# Sheet1.net
KiCad netlist of a schematic drawn in Altium Designer
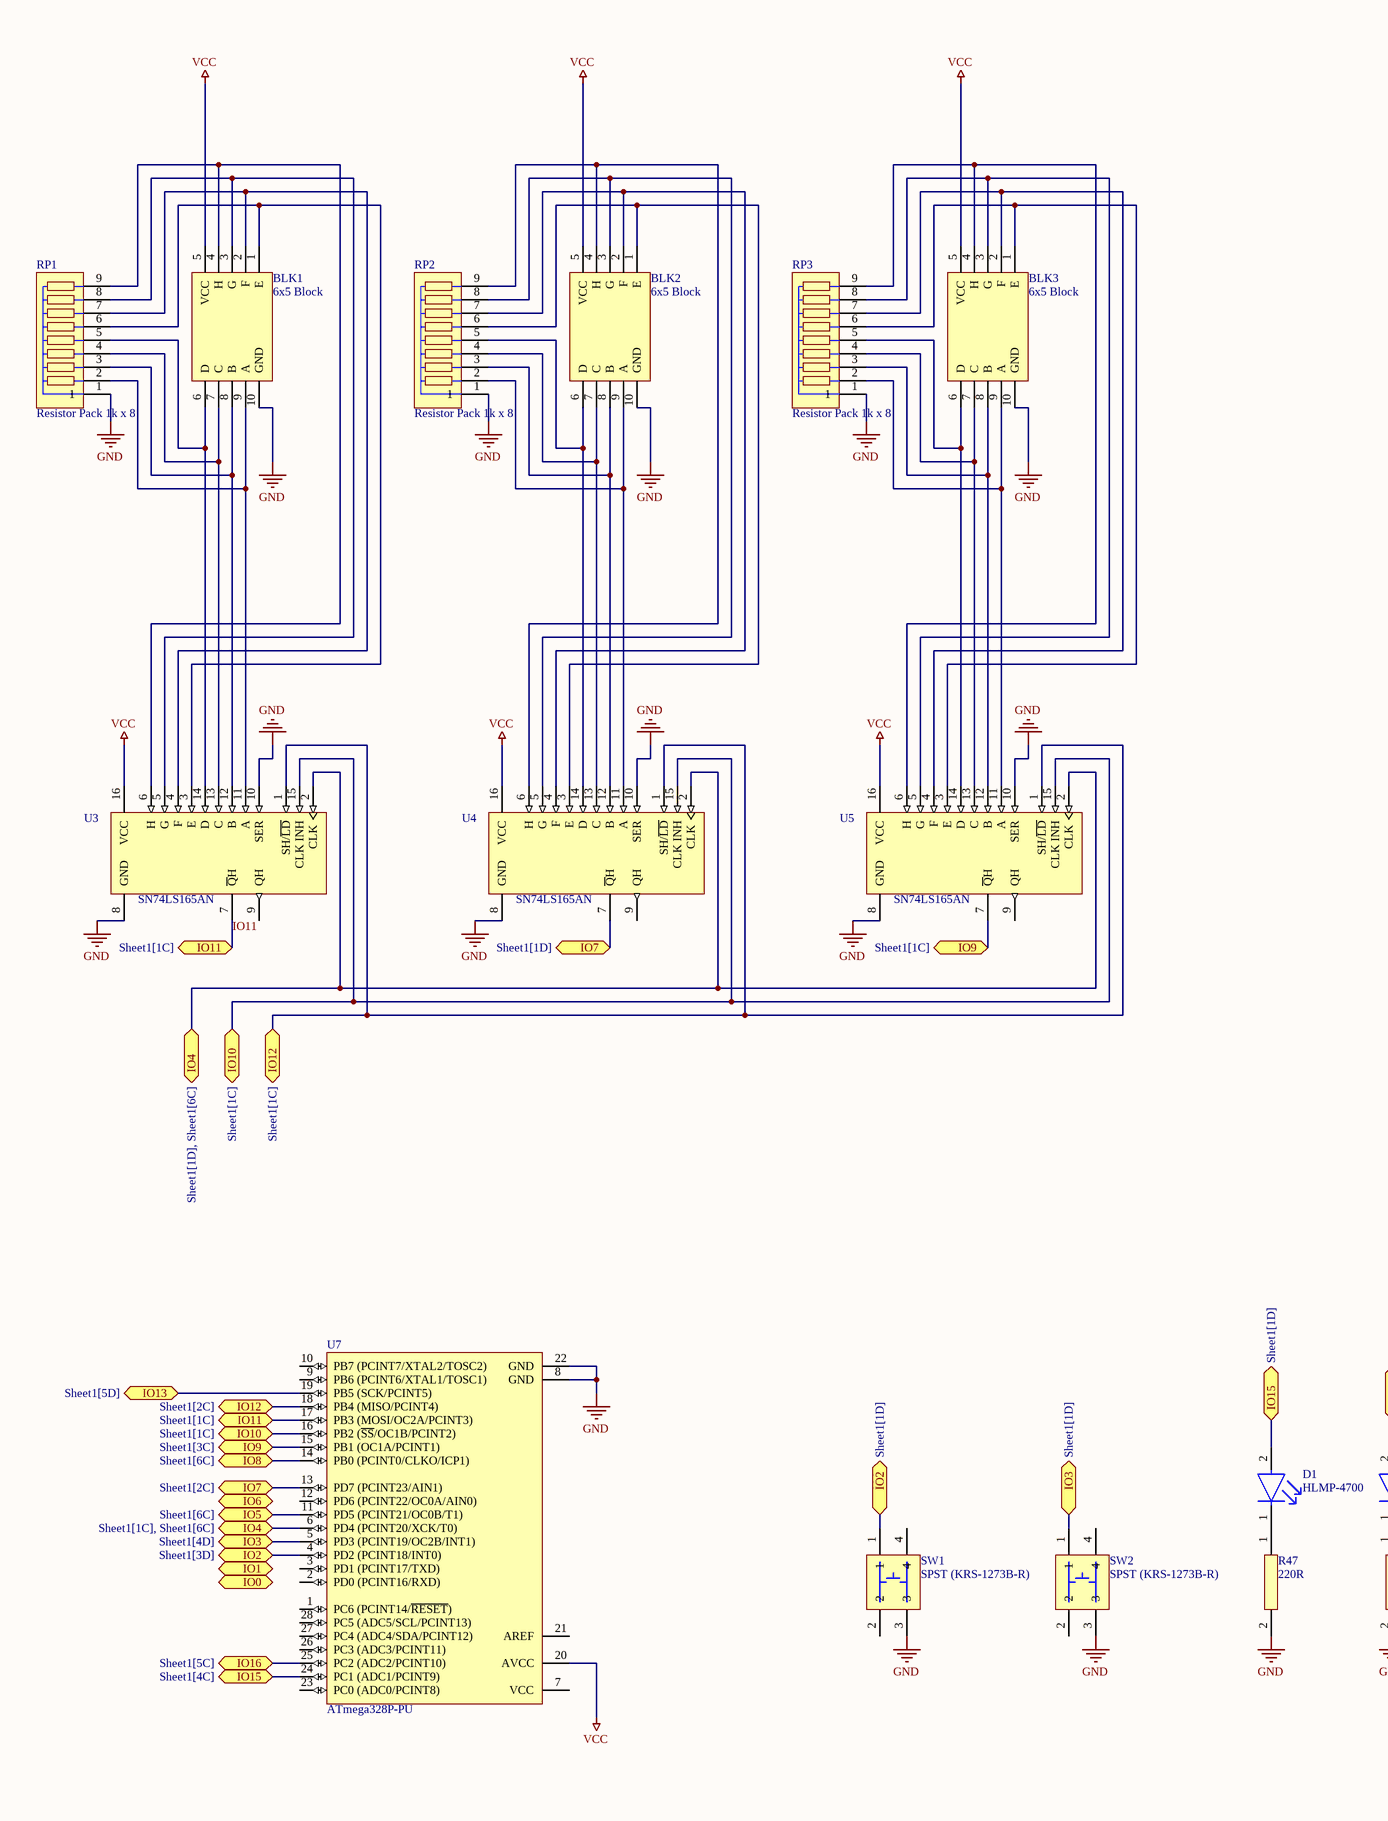
[diagram p0: Sheet1.SchDoc, left]
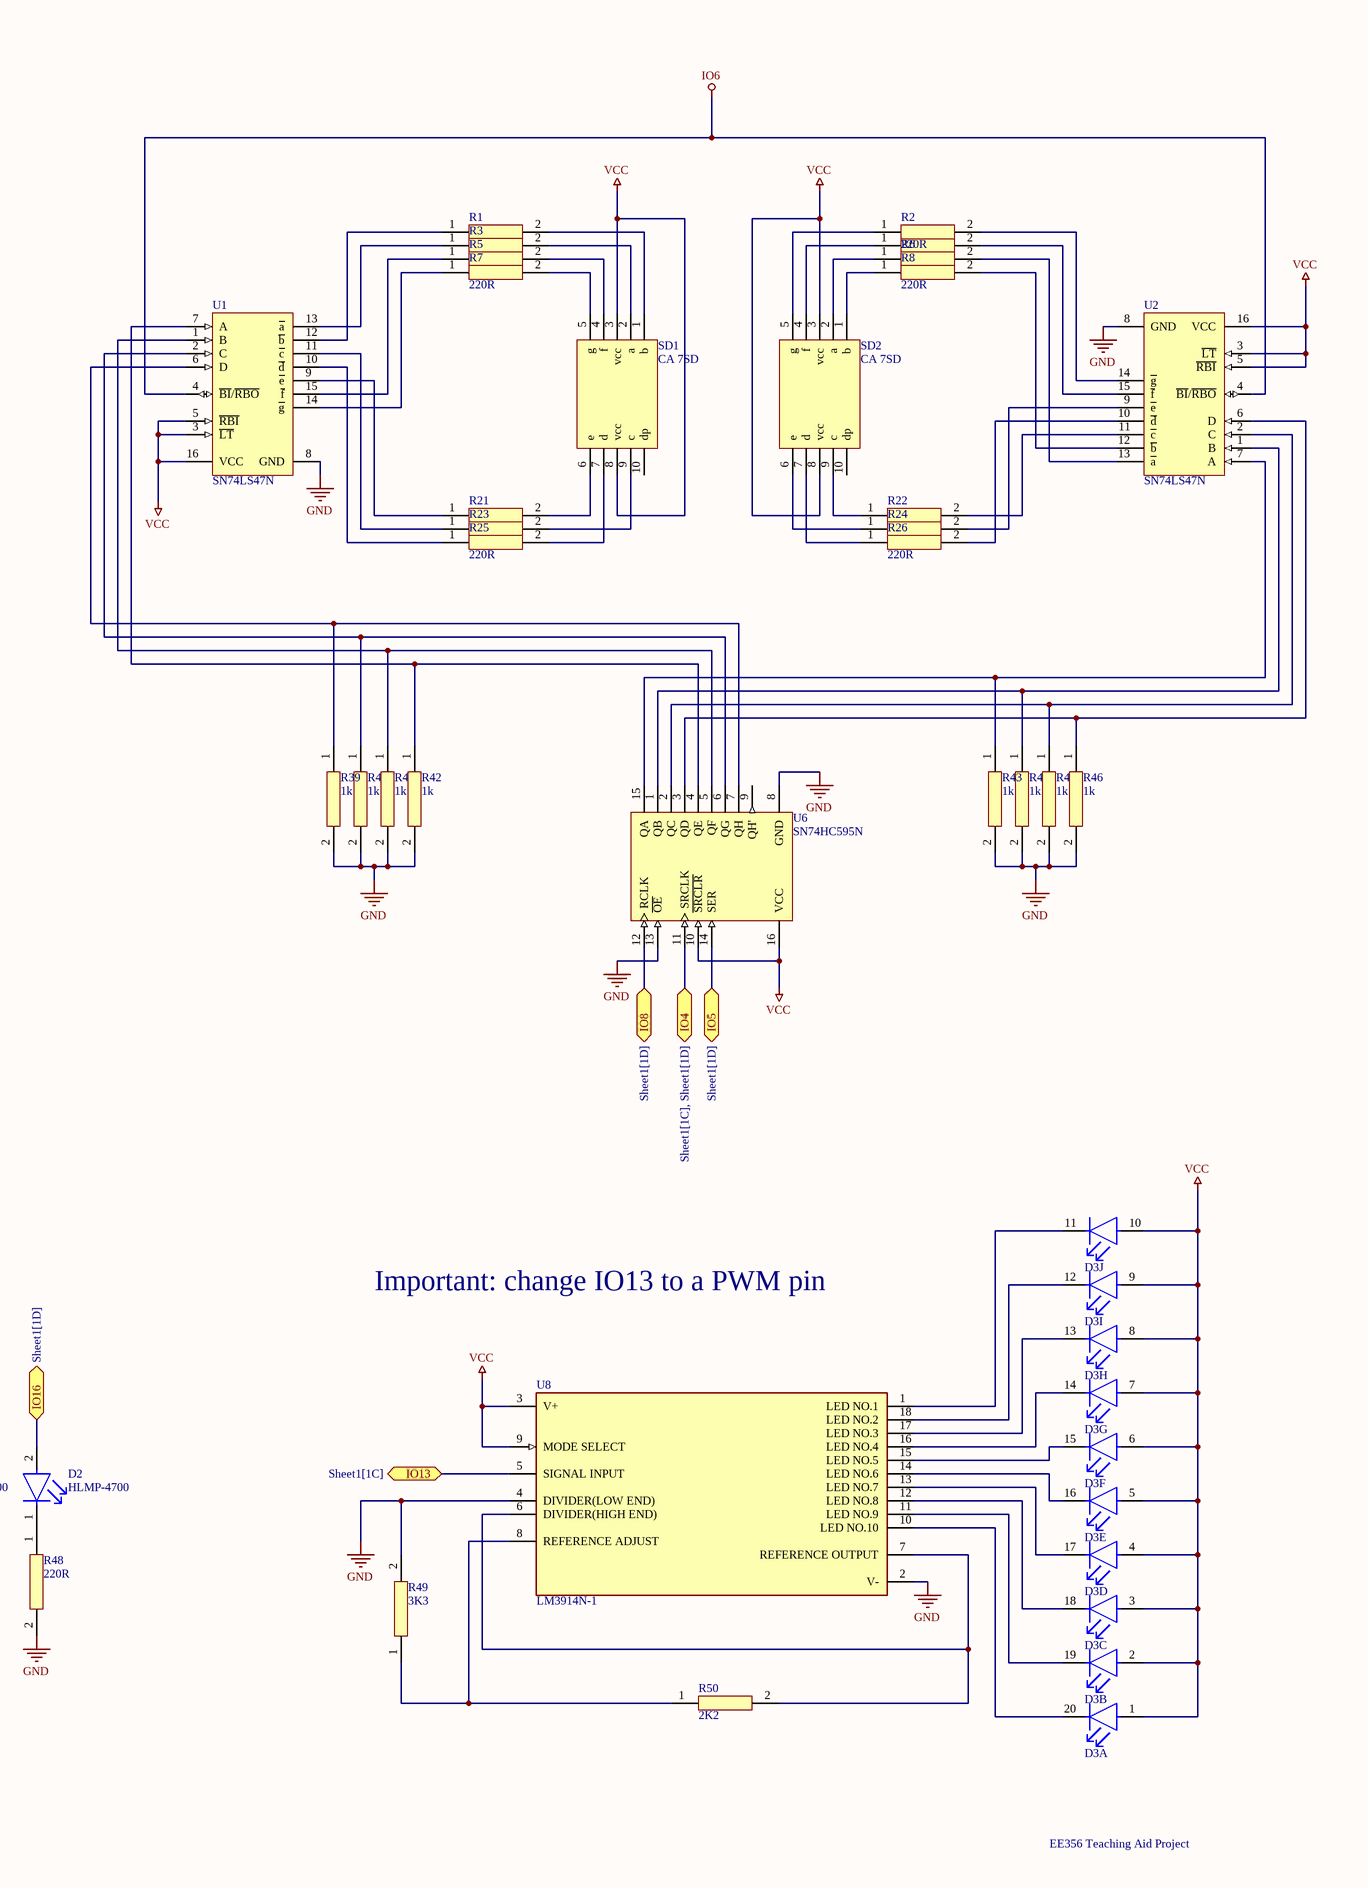
[diagram p1: Sheet1.SchDoc, right]

(export (version "E")
  (design (tool "Eeschema 10.0.6"))
  (components
    (comp (ref "BLK1")
      (value "6x5 Block")
      (footprint "Block_6x5")
      (libsource (lib "Schlib1") (part "Block_6x5"))
    )
    (comp (ref "BLK2")
      (value "6x5 Block")
      (footprint "Block_6x5")
      (libsource (lib "Schlib1") (part "Block_6x5"))
    )
    (comp (ref "BLK3")
      (value "6x5 Block")
      (footprint "Block_6x5")
      (libsource (lib "Schlib1") (part "Block_6x5"))
    )
    (comp (ref "D1")
      (value "HLMP-4700")
      (footprint "FP-HLMP-4700-MFG")
      (description "LED RED DIFFUSED T-1 3/4 T/H")
      (fields
        (field (name "OCTOPART") "https://octopart.com/hlmp-4700-broadcom-71130526")
        (field (name "MANUFACTURER") "Broadcom")
      )
      (libsource (lib "Altium Content Vault") (part "8706943c75ba83719d021d2fdc84c58"))
    )
    (comp (ref "D2")
      (value "HLMP-4700")
      (footprint "FP-HLMP-4700-MFG")
      (description "LED RED DIFFUSED T-1 3/4 T/H")
      (fields
        (field (name "OCTOPART") "https://octopart.com/hlmp-4700-broadcom-71130526")
        (field (name "MANUFACTURER") "Broadcom")
      )
      (libsource (lib "Altium Content Vault") (part "8706943c75ba83719d021d2fdc84c58"))
    )
    (comp (ref "D3")
      (value "SSA-LXB10HW-GF/LP")
      (footprint "FP-SSA-LXB10HW-GF-LP-MFG")
      (description "LED ARRAY 10X25MM 10SEG RED DIFF")
      (fields
        (field (name "OCTOPART") "https://octopart.com/ssa-lxb10hw-gf%2Flp-lumex-548235")
        (field (name "MANUFACTURER") "lumex")
      )
      (libsource (lib "Altium Content Vault") (part "0ad3f8813297581e4dba16f0763b6c7"))
    )
    (comp (ref "R1")
      (value "220R")
      (footprint "CFR_400mil")
      (description "General Type Carbon Film Resistor 220Ohm 1/4W 5% Axial Bulk")
      (fields
        (field (name "MANUFACTURER") "Yageo")
        (field (name "MANUFACTURER PART NUMBER") "CFR-25JB-52-220R")
      )
      (libsource (lib "Schlib1") (part "CFR-25JB-52-220R"))
    )
    (comp (ref "R2")
      (value "220R")
      (footprint "CFR_400mil")
      (description "General Type Carbon Film Resistor 220Ohm 1/4W 5% Axial Bulk")
      (fields
        (field (name "MANUFACTURER") "Yageo")
        (field (name "MANUFACTURER PART NUMBER") "CFR-25JB-52-220R")
      )
      (libsource (lib "Schlib1") (part "CFR-25JB-52-220R"))
    )
    (comp (ref "R3")
      (value "220R")
      (footprint "CFR_400mil")
      (description "General Type Carbon Film Resistor 220Ohm 1/4W 5% Axial Bulk")
      (fields
        (field (name "MANUFACTURER") "Yageo")
        (field (name "MANUFACTURER PART NUMBER") "CFR-25JB-52-220R")
      )
      (libsource (lib "Schlib1") (part "CFR-25JB-52-220R"))
    )
    (comp (ref "R4")
      (value "220R")
      (footprint "CFR_400mil")
      (description "General Type Carbon Film Resistor 220Ohm 1/4W 5% Axial Bulk")
      (fields
        (field (name "MANUFACTURER") "Yageo")
        (field (name "MANUFACTURER PART NUMBER") "CFR-25JB-52-220R")
      )
      (libsource (lib "Schlib1") (part "CFR-25JB-52-220R"))
    )
    (comp (ref "R5")
      (value "220R")
      (footprint "CFR_400mil")
      (description "General Type Carbon Film Resistor 220Ohm 1/4W 5% Axial Bulk")
      (fields
        (field (name "MANUFACTURER") "Yageo")
        (field (name "MANUFACTURER PART NUMBER") "CFR-25JB-52-220R")
      )
      (libsource (lib "Schlib1") (part "CFR-25JB-52-220R"))
    )
    (comp (ref "R6")
      (value "220R")
      (footprint "CFR_400mil")
      (description "General Type Carbon Film Resistor 220Ohm 1/4W 5% Axial Bulk")
      (fields
        (field (name "MANUFACTURER") "Yageo")
        (field (name "MANUFACTURER PART NUMBER") "CFR-25JB-52-220R")
      )
      (libsource (lib "Schlib1") (part "CFR-25JB-52-220R"))
    )
    (comp (ref "R7")
      (value "220R")
      (footprint "CFR_400mil")
      (description "General Type Carbon Film Resistor 220Ohm 1/4W 5% Axial Bulk")
      (fields
        (field (name "MANUFACTURER") "Yageo")
        (field (name "MANUFACTURER PART NUMBER") "CFR-25JB-52-220R")
      )
      (libsource (lib "Schlib1") (part "CFR-25JB-52-220R"))
    )
    (comp (ref "R8")
      (value "220R")
      (footprint "CFR_400mil")
      (description "General Type Carbon Film Resistor 220Ohm 1/4W 5% Axial Bulk")
      (fields
        (field (name "MANUFACTURER") "Yageo")
        (field (name "MANUFACTURER PART NUMBER") "CFR-25JB-52-220R")
      )
      (libsource (lib "Schlib1") (part "CFR-25JB-52-220R"))
    )
    (comp (ref "R21")
      (value "220R")
      (footprint "CFR_400mil")
      (description "General Type Carbon Film Resistor 220Ohm 1/4W 5% Axial Bulk")
      (fields
        (field (name "MANUFACTURER") "Yageo")
        (field (name "MANUFACTURER PART NUMBER") "CFR-25JB-52-220R")
      )
      (libsource (lib "Schlib1") (part "CFR-25JB-52-220R"))
    )
    (comp (ref "R22")
      (value "220R")
      (footprint "CFR_400mil")
      (description "General Type Carbon Film Resistor 220Ohm 1/4W 5% Axial Bulk")
      (fields
        (field (name "MANUFACTURER") "Yageo")
        (field (name "MANUFACTURER PART NUMBER") "CFR-25JB-52-220R")
      )
      (libsource (lib "Schlib1") (part "CFR-25JB-52-220R"))
    )
    (comp (ref "R23")
      (value "220R")
      (footprint "CFR_400mil")
      (description "General Type Carbon Film Resistor 220Ohm 1/4W 5% Axial Bulk")
      (fields
        (field (name "MANUFACTURER") "Yageo")
        (field (name "MANUFACTURER PART NUMBER") "CFR-25JB-52-220R")
      )
      (libsource (lib "Schlib1") (part "CFR-25JB-52-220R"))
    )
    (comp (ref "R24")
      (value "220R")
      (footprint "CFR_400mil")
      (description "General Type Carbon Film Resistor 220Ohm 1/4W 5% Axial Bulk")
      (fields
        (field (name "MANUFACTURER") "Yageo")
        (field (name "MANUFACTURER PART NUMBER") "CFR-25JB-52-220R")
      )
      (libsource (lib "Schlib1") (part "CFR-25JB-52-220R"))
    )
    (comp (ref "R25")
      (value "220R")
      (footprint "CFR_400mil")
      (description "General Type Carbon Film Resistor 220Ohm 1/4W 5% Axial Bulk")
      (fields
        (field (name "MANUFACTURER") "Yageo")
        (field (name "MANUFACTURER PART NUMBER") "CFR-25JB-52-220R")
      )
      (libsource (lib "Schlib1") (part "CFR-25JB-52-220R"))
    )
    (comp (ref "R26")
      (value "220R")
      (footprint "CFR_400mil")
      (description "General Type Carbon Film Resistor 220Ohm 1/4W 5% Axial Bulk")
      (fields
        (field (name "MANUFACTURER") "Yageo")
        (field (name "MANUFACTURER PART NUMBER") "CFR-25JB-52-220R")
      )
      (libsource (lib "Schlib1") (part "CFR-25JB-52-220R"))
    )
    (comp (ref "R39")
      (value "1k")
      (footprint "CFR_400mil")
      (description "Res Carbon Film 1K Ohm 5% 1/4W -350ppm/°C to 350ppm/°C Conformal AXL Thru-Hole Bulk")
      (fields
        (field (name "MANUFACTURER") "Yageo")
        (field (name "MANUFACTURER PART NUMBER") "CFR-25JB-52-1K")
      )
      (libsource (lib "Schlib1") (part "CFR-25JB-52-1K"))
    )
    (comp (ref "R40")
      (value "1k")
      (footprint "CFR_400mil")
      (description "Res Carbon Film 1K Ohm 5% 1/4W -350ppm/°C to 350ppm/°C Conformal AXL Thru-Hole Bulk")
      (fields
        (field (name "MANUFACTURER") "Yageo")
        (field (name "MANUFACTURER PART NUMBER") "CFR-25JB-52-1K")
      )
      (libsource (lib "Schlib1") (part "CFR-25JB-52-1K"))
    )
    (comp (ref "R41")
      (value "1k")
      (footprint "CFR_400mil")
      (description "Res Carbon Film 1K Ohm 5% 1/4W -350ppm/°C to 350ppm/°C Conformal AXL Thru-Hole Bulk")
      (fields
        (field (name "MANUFACTURER") "Yageo")
        (field (name "MANUFACTURER PART NUMBER") "CFR-25JB-52-1K")
      )
      (libsource (lib "Schlib1") (part "CFR-25JB-52-1K"))
    )
    (comp (ref "R42")
      (value "1k")
      (footprint "CFR_400mil")
      (description "Res Carbon Film 1K Ohm 5% 1/4W -350ppm/°C to 350ppm/°C Conformal AXL Thru-Hole Bulk")
      (fields
        (field (name "MANUFACTURER") "Yageo")
        (field (name "MANUFACTURER PART NUMBER") "CFR-25JB-52-1K")
      )
      (libsource (lib "Schlib1") (part "CFR-25JB-52-1K"))
    )
    (comp (ref "R43")
      (value "1k")
      (footprint "CFR_400mil")
      (description "Res Carbon Film 1K Ohm 5% 1/4W -350ppm/°C to 350ppm/°C Conformal AXL Thru-Hole Bulk")
      (fields
        (field (name "MANUFACTURER") "Yageo")
        (field (name "MANUFACTURER PART NUMBER") "CFR-25JB-52-1K")
      )
      (libsource (lib "Schlib1") (part "CFR-25JB-52-1K"))
    )
    (comp (ref "R44")
      (value "1k")
      (footprint "CFR_400mil")
      (description "Res Carbon Film 1K Ohm 5% 1/4W -350ppm/°C to 350ppm/°C Conformal AXL Thru-Hole Bulk")
      (fields
        (field (name "MANUFACTURER") "Yageo")
        (field (name "MANUFACTURER PART NUMBER") "CFR-25JB-52-1K")
      )
      (libsource (lib "Schlib1") (part "CFR-25JB-52-1K"))
    )
    (comp (ref "R45")
      (value "1k")
      (footprint "CFR_400mil")
      (description "Res Carbon Film 1K Ohm 5% 1/4W -350ppm/°C to 350ppm/°C Conformal AXL Thru-Hole Bulk")
      (fields
        (field (name "MANUFACTURER") "Yageo")
        (field (name "MANUFACTURER PART NUMBER") "CFR-25JB-52-1K")
      )
      (libsource (lib "Schlib1") (part "CFR-25JB-52-1K"))
    )
    (comp (ref "R46")
      (value "1k")
      (footprint "CFR_400mil")
      (description "Res Carbon Film 1K Ohm 5% 1/4W -350ppm/°C to 350ppm/°C Conformal AXL Thru-Hole Bulk")
      (fields
        (field (name "MANUFACTURER") "Yageo")
        (field (name "MANUFACTURER PART NUMBER") "CFR-25JB-52-1K")
      )
      (libsource (lib "Schlib1") (part "CFR-25JB-52-1K"))
    )
    (comp (ref "R47")
      (value "220R")
      (footprint "CFR_400mil")
      (description "General Type Carbon Film Resistor 220Ohm 1/4W 5% Axial Bulk")
      (fields
        (field (name "MANUFACTURER") "Yageo")
        (field (name "MANUFACTURER PART NUMBER") "CFR-25JB-52-220R")
      )
      (libsource (lib "") (part "CFR-25JB-52-220R_1"))
    )
    (comp (ref "R48")
      (value "220R")
      (footprint "CFR_400mil")
      (description "General Type Carbon Film Resistor 220Ohm 1/4W 5% Axial Bulk")
      (fields
        (field (name "MANUFACTURER") "Yageo")
        (field (name "MANUFACTURER PART NUMBER") "CFR-25JB-52-220R")
      )
      (libsource (lib "") (part "CFR-25JB-52-220R_1"))
    )
    (comp (ref "R49")
      (value "3K3")
      (footprint "CFR_400mil")
      (description "General Type Carbon Film Resistor 3.3kOhm 1/4W 5% Axial Bulk")
      (fields
        (field (name "MANUFACTURER") "Yageo")
        (field (name "MANUFACTURER PART NUMBER") "CFR-25JB-52-220R")
      )
      (libsource (lib "Schlib1") (part "CFR-25JB-52-3K3"))
    )
    (comp (ref "R50")
      (value "2K2")
      (footprint "CFR_400mil")
      (description "General Type Carbon Film Resistor 2.2kOhm 1/4W 5% Axial Bulk")
      (fields
        (field (name "MANUFACTURER") "Yageo")
        (field (name "MANUFACTURER PART NUMBER") "CFR-25JB-52-220R")
      )
      (libsource (lib "Schlib1") (part "CFR-25JB-52-2K2"))
    )
    (comp (ref "RP1")
      (value "Resistor Pack 1k x 8")
      (footprint "Resistor Pack 1k x 8")
      (description "Res Thick Film NET 1K Ohm 2% 1.13W ±100ppm/°C BUS Molded 9-Pin SIP Pin Thru-Hole")
      (fields
        (field (name "MANUFACTURER") "Bourns")
        (field (name "MANUFACTURER PART NUMBER") "4309R-101-102LF")
      )
      (libsource (lib "Schlib1") (part "4309R-101-102LF"))
    )
    (comp (ref "RP2")
      (value "Resistor Pack 1k x 8")
      (footprint "Resistor Pack 1k x 8")
      (description "Res Thick Film NET 1K Ohm 2% 1.13W ±100ppm/°C BUS Molded 9-Pin SIP Pin Thru-Hole")
      (fields
        (field (name "MANUFACTURER") "Bourns")
        (field (name "MANUFACTURER PART NUMBER") "4309R-101-102LF")
      )
      (libsource (lib "Schlib1") (part "4309R-101-102LF"))
    )
    (comp (ref "RP3")
      (value "Resistor Pack 1k x 8")
      (footprint "Resistor Pack 1k x 8")
      (description "Res Thick Film NET 1K Ohm 2% 1.13W ±100ppm/°C BUS Molded 9-Pin SIP Pin Thru-Hole")
      (fields
        (field (name "MANUFACTURER") "Bourns")
        (field (name "MANUFACTURER PART NUMBER") "4309R-101-102LF")
      )
      (libsource (lib "Schlib1") (part "4309R-101-102LF"))
    )
    (comp (ref "SD1")
      (value "CA 7SD")
      (footprint "CA 7SD")
      (description "Single Digit Seven Segment Green 0.56\" Common Anode Through Hole LED Display")
      (fields (field (name "MANUFACTURER") "Lumex") (field (name "MANUFACTURER PART NUMBER") "LDS-A5642RI"))
      (libsource (lib "Schlib1") (part "LDS-A5642RI"))
    )
    (comp (ref "SD2")
      (value "CA 7SD")
      (footprint "CA 7SD")
      (description "Single Digit Seven Segment Green 0.56\" Common Anode Through Hole LED Display")
      (fields (field (name "MANUFACTURER") "Lumex") (field (name "MANUFACTURER PART NUMBER") "LDS-A5642RI"))
      (libsource (lib "Schlib1") (part "LDS-A5642RI"))
    )
    (comp (ref "SW1")
      (value "SPST (KRS-1273B-R)")
      (footprint "SPST KRS-1273B-R")
      (description "Switch Push Button Tactile Off Momentary (On) Single Pole Single Throw Cap: 155389 155409")
      (fields
        (field (name "MANUFACTURER") "Jameco Valuepro")
        (field (name "MANUFACTURER PART NUMBER") "KRS-1273B-R")
      )
      (libsource (lib "Schlib1") (part "KRS-1273B-R"))
    )
    (comp (ref "SW2")
      (value "SPST (KRS-1273B-R)")
      (footprint "SPST KRS-1273B-R")
      (description "Switch Push Button Tactile Off Momentary (On) Single Pole Single Throw Cap: 155389 155409")
      (fields
        (field (name "MANUFACTURER") "Jameco Valuepro")
        (field (name "MANUFACTURER PART NUMBER") "KRS-1273B-R")
      )
      (libsource (lib "Schlib1") (part "KRS-1273B-R"))
    )
    (comp (ref "U1")
      (value "SN74LS47N")
      (footprint "N0016A")
      (description "BCD-to-7-Segment Decoder / Driver, 4.75 to 5.25 V, 0 to 70 degC, 16-pin DIP (N16), Pb-Free (RoHS)")
      (fields (field (name "MANUFACTURER") "Texas Instruments"))
      (libsource (lib "") (part "TI-SNX4XX247-16_1"))
    )
    (comp (ref "U2")
      (value "SN74LS47N")
      (footprint "N0016A")
      (description "BCD-to-7-Segment Decoder / Driver, 4.75 to 5.25 V, 0 to 70 degC, 16-pin DIP (N16), Pb-Free (RoHS)")
      (fields (field (name "MANUFACTURER") "Texas Instruments"))
      (libsource (lib "Altium Content Vault") (part "TI-SNX4XX247-16"))
    )
    (comp (ref "U3")
      (value "SN74LS165AN")
      (footprint "N0016A")
      (description "Serial-out shift registers, N0016A, TUBE")
      (fields
        (field (name "GENERIC PART NUMBER") "SN74LS165A")
        (field (name "MANUFACTURER") "Texas Instruments")
      )
      (libsource (lib "Altium Content Vault") (part "TI-SNX4XXX165X-16"))
    )
    (comp (ref "U4")
      (value "SN74LS165AN")
      (footprint "N0016A")
      (description "Serial-out shift registers, N0016A, TUBE")
      (fields
        (field (name "GENERIC PART NUMBER") "SN74LS165A")
        (field (name "MANUFACTURER") "Texas Instruments")
      )
      (libsource (lib "Altium Content Vault") (part "TI-SNX4XXX165X-16"))
    )
    (comp (ref "U5")
      (value "SN74LS165AN")
      (footprint "N0016A")
      (description "Serial-out shift registers, N0016A, TUBE")
      (fields
        (field (name "GENERIC PART NUMBER") "SN74LS165A")
        (field (name "MANUFACTURER") "Texas Instruments")
      )
      (libsource (lib "Altium Content Vault") (part "TI-SNX4XXX165X-16"))
    )
    (comp (ref "U6")
      (value "SN74HC595N")
      (footprint "N0016A")
      (description "8-Bit Shift Registers With 3-State Output Registers, N0016A, TUBE")
      (fields
        (field (name "GENERIC PART NUMBER") "SN74HC595")
        (field (name "MANUFACTURER") "Texas Instruments")
      )
      (libsource (lib "Altium Content Vault") (part "TI-SN74XHCT595X_SN74LV595A-16"))
    )
    (comp (ref "U7")
      (value "ATmega328P-PU")
      (footprint "28P3")
      (libsource (lib "Altium Content Vault") (part "MC-8B-ATM48-IL28"))
    )
    (comp (ref "U8")
      (value "LM3914N-1")
      (footprint "FP-NFK0018A-MFG")
      (description "IC DRVR DOT/BAR DISPLAY 18DIP")
      (libsource (lib "Altium Content Vault") (part "8d9105b9cf50def005be23956edfdd2"))
    )
  )
  (nets
    (net (code "3") (name "/IO2") (class "Default")
      (node (ref "SW1") (pin "1") (pinfunction "1_1") (pintype "passive"))
      (node (ref "U7") (pin "4") (pinfunction "PD2_(PCINT18/INT0)_4") (pintype "bidirectional"))
    )
    (net (code "4") (name "/IO3") (class "Default")
      (node (ref "SW2") (pin "1") (pinfunction "1_1") (pintype "passive"))
      (node (ref "U7") (pin "5") (pinfunction "PD3_(PCINT19/OC2B/INT1)_5") (pintype "bidirectional"))
    )
    (net (code "5") (name "/IO4") (class "Default")
      (node (ref "U3") (pin "2") (pinfunction "CLK_2") (pintype "input"))
      (node (ref "U4") (pin "2") (pinfunction "CLK_2") (pintype "input"))
      (node (ref "U5") (pin "2") (pinfunction "CLK_2") (pintype "input"))
      (node (ref "U6") (pin "11") (pinfunction "SRCLK_11") (pintype "input"))
      (node (ref "U7") (pin "6") (pinfunction "PD4_(PCINT20/XCK/T0)_6") (pintype "bidirectional"))
    )
    (net (code "6") (name "/IO5") (class "Default")
      (node (ref "U6") (pin "14") (pinfunction "SER_14") (pintype "input"))
      (node (ref "U7") (pin "11") (pinfunction "PD5_(PCINT21/OC0B/T1)_11") (pintype "bidirectional"))
    )
    (net (code "7") (name "/IO7") (class "Default")
      (node (ref "U4") (pin "7") (pinfunction "~{Q}H_7") (pintype "passive"))
      (node (ref "U7") (pin "13") (pinfunction "PD7_(PCINT23/AIN1)_13") (pintype "bidirectional"))
    )
    (net (code "8") (name "/IO8") (class "Default")
      (node (ref "U6") (pin "12") (pinfunction "RCLK_12") (pintype "input"))
      (node (ref "U7") (pin "14") (pinfunction "PB0_(PCINT0/CLKO/ICP1)_14") (pintype "bidirectional"))
    )
    (net (code "9") (name "/IO9") (class "Default")
      (node (ref "U5") (pin "7") (pinfunction "~{Q}H_7") (pintype "passive"))
      (node (ref "U7") (pin "15") (pinfunction "PB1_(OC1A/PCINT1)_15") (pintype "bidirectional"))
    )
    (net (code "10") (name "/IO10") (class "Default")
      (node (ref "U3") (pin "15") (pinfunction "CLK_INH_15") (pintype "input"))
      (node (ref "U4") (pin "15") (pinfunction "CLK_INH_15") (pintype "input"))
      (node (ref "U5") (pin "15") (pinfunction "CLK_INH_15") (pintype "input"))
      (node (ref "U7") (pin "16") (pinfunction "PB2_(~{SS}/OC1B/PCINT2)_16") (pintype "bidirectional"))
    )
    (net (code "11") (name "/IO11") (class "Default")
      (node (ref "U3") (pin "7") (pinfunction "~{Q}H_7") (pintype "passive"))
      (node (ref "U7") (pin "17") (pinfunction "PB3_(MOSI/OC2A/PCINT3)_17") (pintype "bidirectional"))
    )
    (net (code "12") (name "/IO12") (class "Default")
      (node (ref "U3") (pin "1") (pinfunction "SH/~{LD}_1") (pintype "input"))
      (node (ref "U4") (pin "1") (pinfunction "SH/~{LD}_1") (pintype "input"))
      (node (ref "U5") (pin "1") (pinfunction "SH/~{LD}_1") (pintype "input"))
      (node (ref "U7") (pin "18") (pinfunction "PB4_(MISO/PCINT4)_18") (pintype "bidirectional"))
    )
    (net (code "13") (name "/IO13") (class "Default")
      (node (ref "U7") (pin "19") (pinfunction "PB5_(SCK/PCINT5)_19") (pintype "bidirectional"))
      (node (ref "U8") (pin "5") (pinfunction "SIGNAL_INPUT_5") (pintype "passive"))
    )
    (net (code "14") (name "/IO15") (class "Default")
      (node (ref "D1") (pin "2") (pinfunction "A_2") (pintype "passive"))
      (node (ref "U7") (pin "24") (pinfunction "PC1_(ADC1/PCINT9)_24") (pintype "bidirectional"))
    )
    (net (code "15") (name "/IO16") (class "Default")
      (node (ref "D2") (pin "2") (pinfunction "A_2") (pintype "passive"))
      (node (ref "U7") (pin "25") (pinfunction "PC2_(ADC2/PCINT10)_25") (pintype "bidirectional"))
    )
    (net (code "16") (name "GND") (class "Default")
      (node (ref "BLK1") (pin "10") (pinfunction "GND_10") (pintype "passive"))
      (node (ref "BLK2") (pin "10") (pinfunction "GND_10") (pintype "passive"))
      (node (ref "BLK3") (pin "10") (pinfunction "GND_10") (pintype "passive"))
      (node (ref "R39") (pin "2") (pinfunction "2_2") (pintype "passive"))
      (node (ref "R40") (pin "2") (pinfunction "2_2") (pintype "passive"))
      (node (ref "R41") (pin "2") (pinfunction "2_2") (pintype "passive"))
      (node (ref "R42") (pin "2") (pinfunction "2_2") (pintype "passive"))
      (node (ref "R43") (pin "2") (pinfunction "2_2") (pintype "passive"))
      (node (ref "R44") (pin "2") (pinfunction "2_2") (pintype "passive"))
      (node (ref "R45") (pin "2") (pinfunction "2_2") (pintype "passive"))
      (node (ref "R46") (pin "2") (pinfunction "2_2") (pintype "passive"))
      (node (ref "R47") (pin "2") (pinfunction "2_2") (pintype "passive"))
      (node (ref "R48") (pin "2") (pinfunction "2_2") (pintype "passive"))
      (node (ref "R49") (pin "2") (pinfunction "2_2") (pintype "passive"))
      (node (ref "RP1") (pin "1") (pinfunction "1_1") (pintype "passive"))
      (node (ref "RP2") (pin "1") (pinfunction "1_1") (pintype "passive"))
      (node (ref "RP3") (pin "1") (pinfunction "1_1") (pintype "passive"))
      (node (ref "SW1") (pin "3") (pinfunction "3_3") (pintype "passive"))
      (node (ref "SW2") (pin "3") (pinfunction "3_3") (pintype "passive"))
      (node (ref "U1") (pin "8") (pinfunction "GND_8") (pintype "power_in"))
      (node (ref "U2") (pin "8") (pinfunction "GND_8") (pintype "power_in"))
      (node (ref "U3") (pin "10") (pinfunction "SER_10") (pintype "input"))
      (node (ref "U3") (pin "8") (pinfunction "GND_8") (pintype "power_in"))
      (node (ref "U4") (pin "10") (pinfunction "SER_10") (pintype "input"))
      (node (ref "U4") (pin "8") (pinfunction "GND_8") (pintype "power_in"))
      (node (ref "U5") (pin "10") (pinfunction "SER_10") (pintype "input"))
      (node (ref "U5") (pin "8") (pinfunction "GND_8") (pintype "power_in"))
      (node (ref "U6") (pin "13") (pinfunction "~{OE}_13") (pintype "input"))
      (node (ref "U6") (pin "8") (pinfunction "GND_8") (pintype "power_in"))
      (node (ref "U7") (pin "22") (pinfunction "GND_22") (pintype "power_in"))
      (node (ref "U7") (pin "8") (pinfunction "GND_8") (pintype "power_in"))
      (node (ref "U8") (pin "2") (pinfunction "V-_2") (pintype "power_in"))
      (node (ref "U8") (pin "4") (pinfunction "DIVIDER(LOW_END)_4") (pintype "passive"))
    )
    (net (code "17") (name "IO6") (class "Default")
      (node (ref "U1") (pin "4") (pinfunction "~{BI}/~{RBO}_4") (pintype "bidirectional"))
      (node (ref "U2") (pin "4") (pinfunction "~{BI}/~{RBO}_4") (pintype "bidirectional"))
    )
    (net (code "18") (name "Net-(BLK1-A)") (class "Default")
      (node (ref "BLK1") (pin "9") (pinfunction "A_9") (pintype "passive"))
      (node (ref "RP1") (pin "2") (pinfunction "2_2") (pintype "passive"))
      (node (ref "U3") (pin "11") (pinfunction "A_11") (pintype "input"))
    )
    (net (code "19") (name "Net-(BLK1-B)") (class "Default")
      (node (ref "BLK1") (pin "8") (pinfunction "B_8") (pintype "passive"))
      (node (ref "RP1") (pin "3") (pinfunction "3_3") (pintype "passive"))
      (node (ref "U3") (pin "12") (pinfunction "B_12") (pintype "input"))
    )
    (net (code "20") (name "Net-(BLK1-C)") (class "Default")
      (node (ref "BLK1") (pin "7") (pinfunction "C_7") (pintype "passive"))
      (node (ref "RP1") (pin "4") (pinfunction "4_4") (pintype "passive"))
      (node (ref "U3") (pin "13") (pinfunction "C_13") (pintype "input"))
    )
    (net (code "21") (name "Net-(BLK1-D)") (class "Default")
      (node (ref "BLK1") (pin "6") (pinfunction "D_6") (pintype "passive"))
      (node (ref "RP1") (pin "5") (pinfunction "5_5") (pintype "passive"))
      (node (ref "U3") (pin "14") (pinfunction "D_14") (pintype "input"))
    )
    (net (code "22") (name "Net-(BLK1-E)") (class "Default")
      (node (ref "BLK1") (pin "1") (pinfunction "E_1") (pintype "passive"))
      (node (ref "RP1") (pin "6") (pinfunction "6_6") (pintype "passive"))
      (node (ref "U3") (pin "3") (pinfunction "E_3") (pintype "input"))
    )
    (net (code "23") (name "Net-(BLK1-F)") (class "Default")
      (node (ref "BLK1") (pin "2") (pinfunction "F_2") (pintype "passive"))
      (node (ref "RP1") (pin "7") (pinfunction "7_7") (pintype "passive"))
      (node (ref "U3") (pin "4") (pinfunction "F_4") (pintype "input"))
    )
    (net (code "24") (name "Net-(BLK1-G)") (class "Default")
      (node (ref "BLK1") (pin "3") (pinfunction "G_3") (pintype "passive"))
      (node (ref "RP1") (pin "8") (pinfunction "8_8") (pintype "passive"))
      (node (ref "U3") (pin "5") (pinfunction "G_5") (pintype "input"))
    )
    (net (code "25") (name "Net-(BLK1-H)") (class "Default")
      (node (ref "BLK1") (pin "4") (pinfunction "H_4") (pintype "passive"))
      (node (ref "RP1") (pin "9") (pinfunction "9_9") (pintype "passive"))
      (node (ref "U3") (pin "6") (pinfunction "H_6") (pintype "input"))
    )
    (net (code "26") (name "Net-(BLK2-A)") (class "Default")
      (node (ref "BLK2") (pin "9") (pinfunction "A_9") (pintype "passive"))
      (node (ref "RP2") (pin "2") (pinfunction "2_2") (pintype "passive"))
      (node (ref "U4") (pin "11") (pinfunction "A_11") (pintype "input"))
    )
    (net (code "27") (name "Net-(BLK2-B)") (class "Default")
      (node (ref "BLK2") (pin "8") (pinfunction "B_8") (pintype "passive"))
      (node (ref "RP2") (pin "3") (pinfunction "3_3") (pintype "passive"))
      (node (ref "U4") (pin "12") (pinfunction "B_12") (pintype "input"))
    )
    (net (code "28") (name "Net-(BLK2-C)") (class "Default")
      (node (ref "BLK2") (pin "7") (pinfunction "C_7") (pintype "passive"))
      (node (ref "RP2") (pin "4") (pinfunction "4_4") (pintype "passive"))
      (node (ref "U4") (pin "13") (pinfunction "C_13") (pintype "input"))
    )
    (net (code "29") (name "Net-(BLK2-D)") (class "Default")
      (node (ref "BLK2") (pin "6") (pinfunction "D_6") (pintype "passive"))
      (node (ref "RP2") (pin "5") (pinfunction "5_5") (pintype "passive"))
      (node (ref "U4") (pin "14") (pinfunction "D_14") (pintype "input"))
    )
    (net (code "30") (name "Net-(BLK2-E)") (class "Default")
      (node (ref "BLK2") (pin "1") (pinfunction "E_1") (pintype "passive"))
      (node (ref "RP2") (pin "6") (pinfunction "6_6") (pintype "passive"))
      (node (ref "U4") (pin "3") (pinfunction "E_3") (pintype "input"))
    )
    (net (code "31") (name "Net-(BLK2-F)") (class "Default")
      (node (ref "BLK2") (pin "2") (pinfunction "F_2") (pintype "passive"))
      (node (ref "RP2") (pin "7") (pinfunction "7_7") (pintype "passive"))
      (node (ref "U4") (pin "4") (pinfunction "F_4") (pintype "input"))
    )
    (net (code "32") (name "Net-(BLK2-G)") (class "Default")
      (node (ref "BLK2") (pin "3") (pinfunction "G_3") (pintype "passive"))
      (node (ref "RP2") (pin "8") (pinfunction "8_8") (pintype "passive"))
      (node (ref "U4") (pin "5") (pinfunction "G_5") (pintype "input"))
    )
    (net (code "33") (name "Net-(BLK2-H)") (class "Default")
      (node (ref "BLK2") (pin "4") (pinfunction "H_4") (pintype "passive"))
      (node (ref "RP2") (pin "9") (pinfunction "9_9") (pintype "passive"))
      (node (ref "U4") (pin "6") (pinfunction "H_6") (pintype "input"))
    )
    (net (code "34") (name "Net-(BLK3-A)") (class "Default")
      (node (ref "BLK3") (pin "9") (pinfunction "A_9") (pintype "passive"))
      (node (ref "RP3") (pin "2") (pinfunction "2_2") (pintype "passive"))
      (node (ref "U5") (pin "11") (pinfunction "A_11") (pintype "input"))
    )
    (net (code "35") (name "Net-(BLK3-B)") (class "Default")
      (node (ref "BLK3") (pin "8") (pinfunction "B_8") (pintype "passive"))
      (node (ref "RP3") (pin "3") (pinfunction "3_3") (pintype "passive"))
      (node (ref "U5") (pin "12") (pinfunction "B_12") (pintype "input"))
    )
    (net (code "36") (name "Net-(BLK3-C)") (class "Default")
      (node (ref "BLK3") (pin "7") (pinfunction "C_7") (pintype "passive"))
      (node (ref "RP3") (pin "4") (pinfunction "4_4") (pintype "passive"))
      (node (ref "U5") (pin "13") (pinfunction "C_13") (pintype "input"))
    )
    (net (code "37") (name "Net-(BLK3-D)") (class "Default")
      (node (ref "BLK3") (pin "6") (pinfunction "D_6") (pintype "passive"))
      (node (ref "RP3") (pin "5") (pinfunction "5_5") (pintype "passive"))
      (node (ref "U5") (pin "14") (pinfunction "D_14") (pintype "input"))
    )
    (net (code "38") (name "Net-(BLK3-E)") (class "Default")
      (node (ref "BLK3") (pin "1") (pinfunction "E_1") (pintype "passive"))
      (node (ref "RP3") (pin "6") (pinfunction "6_6") (pintype "passive"))
      (node (ref "U5") (pin "3") (pinfunction "E_3") (pintype "input"))
    )
    (net (code "39") (name "Net-(BLK3-F)") (class "Default")
      (node (ref "BLK3") (pin "2") (pinfunction "F_2") (pintype "passive"))
      (node (ref "RP3") (pin "7") (pinfunction "7_7") (pintype "passive"))
      (node (ref "U5") (pin "4") (pinfunction "F_4") (pintype "input"))
    )
    (net (code "40") (name "Net-(BLK3-G)") (class "Default")
      (node (ref "BLK3") (pin "3") (pinfunction "G_3") (pintype "passive"))
      (node (ref "RP3") (pin "8") (pinfunction "8_8") (pintype "passive"))
      (node (ref "U5") (pin "5") (pinfunction "G_5") (pintype "input"))
    )
    (net (code "41") (name "Net-(BLK3-H)") (class "Default")
      (node (ref "BLK3") (pin "4") (pinfunction "H_4") (pintype "passive"))
      (node (ref "RP3") (pin "9") (pinfunction "9_9") (pintype "passive"))
      (node (ref "U5") (pin "6") (pinfunction "H_6") (pintype "input"))
    )
    (net (code "42") (name "Net-(D1-C)") (class "Default")
      (node (ref "D1") (pin "1") (pinfunction "C_1") (pintype "passive"))
      (node (ref "R47") (pin "1") (pinfunction "1_1") (pintype "passive"))
    )
    (net (code "43") (name "Net-(D2-C)") (class "Default")
      (node (ref "D2") (pin "1") (pinfunction "C_1") (pintype "passive"))
      (node (ref "R48") (pin "1") (pinfunction "1_1") (pintype "passive"))
    )
    (net (code "44") (name "Net-(D3A-1_CATHODE)") (class "Default")
      (node (ref "D3") (pin "20") (pinfunction "1_CATHODE_20") (pintype "passive"))
      (node (ref "U8") (pin "10") (pinfunction "LED_NO.10_10") (pintype "passive"))
    )
    (net (code "45") (name "Net-(D3B-2_CATHODE)") (class "Default")
      (node (ref "D3") (pin "19") (pinfunction "2_CATHODE_19") (pintype "passive"))
      (node (ref "U8") (pin "11") (pinfunction "LED_NO.9_11") (pintype "passive"))
    )
    (net (code "46") (name "Net-(D3C-3_CATHODE)") (class "Default")
      (node (ref "D3") (pin "18") (pinfunction "3_CATHODE_18") (pintype "passive"))
      (node (ref "U8") (pin "12") (pinfunction "LED_NO.8_12") (pintype "passive"))
    )
    (net (code "47") (name "Net-(D3D-4_CATHODE)") (class "Default")
      (node (ref "D3") (pin "17") (pinfunction "4_CATHODE_17") (pintype "passive"))
      (node (ref "U8") (pin "13") (pinfunction "LED_NO.7_13") (pintype "passive"))
    )
    (net (code "48") (name "Net-(D3E-5_CATHODE)") (class "Default")
      (node (ref "D3") (pin "16") (pinfunction "5_CATHODE_16") (pintype "passive"))
      (node (ref "U8") (pin "14") (pinfunction "LED_NO.6_14") (pintype "passive"))
    )
    (net (code "49") (name "Net-(D3F-6_CATHODE)") (class "Default")
      (node (ref "D3") (pin "15") (pinfunction "6_CATHODE_15") (pintype "passive"))
      (node (ref "U8") (pin "15") (pinfunction "LED_NO.5_15") (pintype "passive"))
    )
    (net (code "50") (name "Net-(D3G-7_CATHODE)") (class "Default")
      (node (ref "D3") (pin "14") (pinfunction "7_CATHODE_14") (pintype "passive"))
      (node (ref "U8") (pin "16") (pinfunction "LED_NO.4_16") (pintype "passive"))
    )
    (net (code "51") (name "Net-(D3H-8_CATHODE)") (class "Default")
      (node (ref "D3") (pin "13") (pinfunction "8_CATHODE_13") (pintype "passive"))
      (node (ref "U8") (pin "17") (pinfunction "LED_NO.3_17") (pintype "passive"))
    )
    (net (code "52") (name "Net-(D3I-9_CATHODE)") (class "Default")
      (node (ref "D3") (pin "12") (pinfunction "9_CATHODE_12") (pintype "passive"))
      (node (ref "U8") (pin "18") (pinfunction "LED_NO.2_18") (pintype "passive"))
    )
    (net (code "53") (name "Net-(D3J-10_CATHODE)") (class "Default")
      (node (ref "D3") (pin "11") (pinfunction "10_CATHODE_11") (pintype "passive"))
      (node (ref "U8") (pin "1") (pinfunction "LED_NO.1_1") (pintype "passive"))
    )
    (net (code "54") (name "Net-(SD1-a)") (class "Default")
      (node (ref "R3") (pin "2") (pinfunction "2_2") (pintype "passive"))
      (node (ref "SD1") (pin "2") (pinfunction "a_2") (pintype "passive"))
    )
    (net (code "55") (name "Net-(SD1-b)") (class "Default")
      (node (ref "R1") (pin "2") (pinfunction "2_2") (pintype "passive"))
      (node (ref "SD1") (pin "1") (pinfunction "b_1") (pintype "passive"))
    )
    (net (code "56") (name "Net-(SD1-c)") (class "Default")
      (node (ref "R23") (pin "2") (pinfunction "2_2") (pintype "passive"))
      (node (ref "SD1") (pin "9") (pinfunction "c_9") (pintype "passive"))
    )
    (net (code "57") (name "Net-(SD1-d)") (class "Default")
      (node (ref "R25") (pin "2") (pinfunction "2_2") (pintype "passive"))
      (node (ref "SD1") (pin "7") (pinfunction "d_7") (pintype "passive"))
    )
    (net (code "58") (name "Net-(SD1-e)") (class "Default")
      (node (ref "R21") (pin "2") (pinfunction "2_2") (pintype "passive"))
      (node (ref "SD1") (pin "6") (pinfunction "e_6") (pintype "passive"))
    )
    (net (code "59") (name "Net-(SD1-f)") (class "Default")
      (node (ref "R5") (pin "2") (pinfunction "2_2") (pintype "passive"))
      (node (ref "SD1") (pin "4") (pinfunction "f_4") (pintype "passive"))
    )
    (net (code "60") (name "Net-(SD1-g)") (class "Default")
      (node (ref "R7") (pin "2") (pinfunction "2_2") (pintype "passive"))
      (node (ref "SD1") (pin "5") (pinfunction "g_5") (pintype "passive"))
    )
    (net (code "61") (name "Net-(SD2-a)") (class "Default")
      (node (ref "R6") (pin "1") (pinfunction "1_1") (pintype "passive"))
      (node (ref "SD2") (pin "2") (pinfunction "a_2") (pintype "passive"))
    )
    (net (code "62") (name "Net-(SD2-b)") (class "Default")
      (node (ref "R8") (pin "1") (pinfunction "1_1") (pintype "passive"))
      (node (ref "SD2") (pin "1") (pinfunction "b_1") (pintype "passive"))
    )
    (net (code "63") (name "Net-(SD2-c)") (class "Default")
      (node (ref "R22") (pin "1") (pinfunction "1_1") (pintype "passive"))
      (node (ref "SD2") (pin "9") (pinfunction "c_9") (pintype "passive"))
    )
    (net (code "64") (name "Net-(SD2-d)") (class "Default")
      (node (ref "R26") (pin "1") (pinfunction "1_1") (pintype "passive"))
      (node (ref "SD2") (pin "7") (pinfunction "d_7") (pintype "passive"))
    )
    (net (code "65") (name "Net-(SD2-e)") (class "Default")
      (node (ref "R24") (pin "1") (pinfunction "1_1") (pintype "passive"))
      (node (ref "SD2") (pin "6") (pinfunction "e_6") (pintype "passive"))
    )
    (net (code "66") (name "Net-(SD2-f)") (class "Default")
      (node (ref "R4") (pin "1") (pinfunction "1_1") (pintype "passive"))
      (node (ref "SD2") (pin "4") (pinfunction "f_4") (pintype "passive"))
    )
    (net (code "67") (name "Net-(SD2-g)") (class "Default")
      (node (ref "R2") (pin "1") (pinfunction "1_1") (pintype "passive"))
      (node (ref "SD2") (pin "5") (pinfunction "g_5") (pintype "passive"))
    )
    (net (code "68") (name "Net-(U1-A)") (class "Default")
      (node (ref "R42") (pin "1") (pinfunction "1_1") (pintype "passive"))
      (node (ref "U1") (pin "7") (pinfunction "A_7") (pintype "input"))
      (node (ref "U6") (pin "4") (pinfunction "QE_4") (pintype "tri_state"))
    )
    (net (code "69") (name "Net-(U1-B)") (class "Default")
      (node (ref "R41") (pin "1") (pinfunction "1_1") (pintype "passive"))
      (node (ref "U1") (pin "1") (pinfunction "B_1") (pintype "input"))
      (node (ref "U6") (pin "5") (pinfunction "QF_5") (pintype "tri_state"))
    )
    (net (code "70") (name "Net-(U1-C)") (class "Default")
      (node (ref "R40") (pin "1") (pinfunction "1_1") (pintype "passive"))
      (node (ref "U1") (pin "2") (pinfunction "C_2") (pintype "input"))
      (node (ref "U6") (pin "6") (pinfunction "QG_6") (pintype "tri_state"))
    )
    (net (code "71") (name "Net-(U1-D)") (class "Default")
      (node (ref "R39") (pin "1") (pinfunction "1_1") (pintype "passive"))
      (node (ref "U1") (pin "6") (pinfunction "D_6") (pintype "input"))
      (node (ref "U6") (pin "7") (pinfunction "QH_7") (pintype "tri_state"))
    )
    (net (code "72") (name "Net-(U1-~{a})") (class "Default")
      (node (ref "R3") (pin "1") (pinfunction "1_1") (pintype "passive"))
      (node (ref "U1") (pin "13") (pinfunction "~{a}_13") (pintype "open_collector"))
    )
    (net (code "73") (name "Net-(U1-~{b})") (class "Default")
      (node (ref "R1") (pin "1") (pinfunction "1_1") (pintype "passive"))
      (node (ref "U1") (pin "12") (pinfunction "~{b}_12") (pintype "open_collector"))
    )
    (net (code "74") (name "Net-(U1-~{c})") (class "Default")
      (node (ref "R23") (pin "1") (pinfunction "1_1") (pintype "passive"))
      (node (ref "U1") (pin "11") (pinfunction "~{c}_11") (pintype "open_collector"))
    )
    (net (code "75") (name "Net-(U1-~{d})") (class "Default")
      (node (ref "R25") (pin "1") (pinfunction "1_1") (pintype "passive"))
      (node (ref "U1") (pin "10") (pinfunction "~{d}_10") (pintype "open_collector"))
    )
    (net (code "76") (name "Net-(U1-~{e})") (class "Default")
      (node (ref "R21") (pin "1") (pinfunction "1_1") (pintype "passive"))
      (node (ref "U1") (pin "9") (pinfunction "~{e}_9") (pintype "open_collector"))
    )
    (net (code "77") (name "Net-(U1-~{f})") (class "Default")
      (node (ref "R5") (pin "1") (pinfunction "1_1") (pintype "passive"))
      (node (ref "U1") (pin "15") (pinfunction "~{f}_15") (pintype "open_collector"))
    )
    (net (code "78") (name "Net-(U1-~{g})") (class "Default")
      (node (ref "R7") (pin "1") (pinfunction "1_1") (pintype "passive"))
      (node (ref "U1") (pin "14") (pinfunction "~{g}_14") (pintype "open_collector"))
    )
    (net (code "79") (name "Net-(U2-A)") (class "Default")
      (node (ref "R43") (pin "1") (pinfunction "1_1") (pintype "passive"))
      (node (ref "U2") (pin "7") (pinfunction "A_7") (pintype "input"))
      (node (ref "U6") (pin "15") (pinfunction "QA_15") (pintype "tri_state"))
    )
    (net (code "80") (name "Net-(U2-B)") (class "Default")
      (node (ref "R44") (pin "1") (pinfunction "1_1") (pintype "passive"))
      (node (ref "U2") (pin "1") (pinfunction "B_1") (pintype "input"))
      (node (ref "U6") (pin "1") (pinfunction "QB_1") (pintype "tri_state"))
    )
    (net (code "81") (name "Net-(U2-C)") (class "Default")
      (node (ref "R45") (pin "1") (pinfunction "1_1") (pintype "passive"))
      (node (ref "U2") (pin "2") (pinfunction "C_2") (pintype "input"))
      (node (ref "U6") (pin "2") (pinfunction "QC_2") (pintype "tri_state"))
    )
    (net (code "82") (name "Net-(U2-D)") (class "Default")
      (node (ref "R46") (pin "1") (pinfunction "1_1") (pintype "passive"))
      (node (ref "U2") (pin "6") (pinfunction "D_6") (pintype "input"))
      (node (ref "U6") (pin "3") (pinfunction "QD_3") (pintype "tri_state"))
    )
    (net (code "83") (name "Net-(U2-~{a})") (class "Default")
      (node (ref "R6") (pin "2") (pinfunction "2_2") (pintype "passive"))
      (node (ref "U2") (pin "13") (pinfunction "~{a}_13") (pintype "open_collector"))
    )
    (net (code "84") (name "Net-(U2-~{b})") (class "Default")
      (node (ref "R8") (pin "2") (pinfunction "2_2") (pintype "passive"))
      (node (ref "U2") (pin "12") (pinfunction "~{b}_12") (pintype "open_collector"))
    )
    (net (code "85") (name "Net-(U2-~{c})") (class "Default")
      (node (ref "R22") (pin "2") (pinfunction "2_2") (pintype "passive"))
      (node (ref "U2") (pin "11") (pinfunction "~{c}_11") (pintype "open_collector"))
    )
    (net (code "86") (name "Net-(U2-~{d})") (class "Default")
      (node (ref "R26") (pin "2") (pinfunction "2_2") (pintype "passive"))
      (node (ref "U2") (pin "10") (pinfunction "~{d}_10") (pintype "open_collector"))
    )
    (net (code "87") (name "Net-(U2-~{e})") (class "Default")
      (node (ref "R24") (pin "2") (pinfunction "2_2") (pintype "passive"))
      (node (ref "U2") (pin "9") (pinfunction "~{e}_9") (pintype "open_collector"))
    )
    (net (code "88") (name "Net-(U2-~{f})") (class "Default")
      (node (ref "R4") (pin "2") (pinfunction "2_2") (pintype "passive"))
      (node (ref "U2") (pin "15") (pinfunction "~{f}_15") (pintype "open_collector"))
    )
    (net (code "89") (name "Net-(U2-~{g})") (class "Default")
      (node (ref "R2") (pin "2") (pinfunction "2_2") (pintype "passive"))
      (node (ref "U2") (pin "14") (pinfunction "~{g}_14") (pintype "open_collector"))
    )
    (net (code "90") (name "Net-(U8-DIVIDER(HIGH_END))") (class "Default")
      (node (ref "R50") (pin "2") (pinfunction "2_2") (pintype "passive"))
      (node (ref "U8") (pin "6") (pinfunction "DIVIDER(HIGH_END)_6") (pintype "passive"))
      (node (ref "U8") (pin "7") (pinfunction "REFERENCE_OUTPUT_7") (pintype "passive"))
    )
    (net (code "91") (name "Net-(U8-REFERENCE_ADJUST)") (class "Default")
      (node (ref "R49") (pin "1") (pinfunction "1_1") (pintype "passive"))
      (node (ref "R50") (pin "1") (pinfunction "1_1") (pintype "passive"))
      (node (ref "U8") (pin "8") (pinfunction "REFERENCE_ADJUST_8") (pintype "passive"))
    )
    (net (code "92") (name "VCC") (class "Default")
      (node (ref "BLK1") (pin "5") (pinfunction "VCC_5") (pintype "passive"))
      (node (ref "BLK2") (pin "5") (pinfunction "VCC_5") (pintype "passive"))
      (node (ref "BLK3") (pin "5") (pinfunction "VCC_5") (pintype "passive"))
      (node (ref "D3") (pin "1") (pinfunction "1_ANODE_1") (pintype "passive"))
      (node (ref "D3") (pin "10") (pinfunction "10_ANODE_10") (pintype "passive"))
      (node (ref "D3") (pin "2") (pinfunction "2_ANODE_2") (pintype "passive"))
      (node (ref "D3") (pin "3") (pinfunction "3_ANODE_3") (pintype "passive"))
      (node (ref "D3") (pin "4") (pinfunction "4_ANODE_4") (pintype "passive"))
      (node (ref "D3") (pin "5") (pinfunction "5_ANODE_5") (pintype "passive"))
      (node (ref "D3") (pin "6") (pinfunction "6_ANODE_6") (pintype "passive"))
      (node (ref "D3") (pin "7") (pinfunction "7_ANODE_7") (pintype "passive"))
      (node (ref "D3") (pin "8") (pinfunction "8_ANODE_8") (pintype "passive"))
      (node (ref "D3") (pin "9") (pinfunction "9_ANODE_9") (pintype "passive"))
      (node (ref "SD1") (pin "3") (pinfunction "vcc_3") (pintype "passive"))
      (node (ref "SD1") (pin "8") (pinfunction "vcc_8") (pintype "passive"))
      (node (ref "SD2") (pin "3") (pinfunction "vcc_3") (pintype "passive"))
      (node (ref "SD2") (pin "8") (pinfunction "vcc_8") (pintype "passive"))
      (node (ref "U1") (pin "16") (pinfunction "VCC_16") (pintype "power_in"))
      (node (ref "U1") (pin "3") (pinfunction "~{LT}_3") (pintype "input"))
      (node (ref "U1") (pin "5") (pinfunction "~{RBI}_5") (pintype "input"))
      (node (ref "U2") (pin "16") (pinfunction "VCC_16") (pintype "power_in"))
      (node (ref "U2") (pin "3") (pinfunction "~{LT}_3") (pintype "input"))
      (node (ref "U2") (pin "5") (pinfunction "~{RBI}_5") (pintype "input"))
      (node (ref "U3") (pin "16") (pinfunction "VCC_16") (pintype "power_in"))
      (node (ref "U4") (pin "16") (pinfunction "VCC_16") (pintype "power_in"))
      (node (ref "U5") (pin "16") (pinfunction "VCC_16") (pintype "power_in"))
      (node (ref "U6") (pin "10") (pinfunction "~{SRCLR}_10") (pintype "input"))
      (node (ref "U6") (pin "16") (pinfunction "VCC_16") (pintype "power_in"))
      (node (ref "U7") (pin "20") (pinfunction "AVCC_20") (pintype "power_in"))
      (node (ref "U8") (pin "3") (pinfunction "V+_3") (pintype "power_in"))
      (node (ref "U8") (pin "9") (pinfunction "MODE_SELECT_9") (pintype "input"))
    )
    (net (code "93") (name "unconnected-(SD1-dp-Pad10)") (class "Default")
      (node (ref "SD1") (pin "10") (pinfunction "dp_10") (pintype "passive"))
    )
    (net (code "94") (name "unconnected-(SD2-dp-Pad10)") (class "Default")
      (node (ref "SD2") (pin "10") (pinfunction "dp_10") (pintype "passive"))
    )
    (net (code "95") (name "unconnected-(SW1-Pad2)") (class "Default")
      (node (ref "SW1") (pin "2") (pinfunction "2_2") (pintype "passive"))
    )
    (net (code "96") (name "unconnected-(SW1-Pad4)") (class "Default")
      (node (ref "SW1") (pin "4") (pinfunction "4_4") (pintype "passive"))
    )
    (net (code "97") (name "unconnected-(SW2-Pad2)") (class "Default")
      (node (ref "SW2") (pin "2") (pinfunction "2_2") (pintype "passive"))
    )
    (net (code "98") (name "unconnected-(SW2-Pad4)") (class "Default")
      (node (ref "SW2") (pin "4") (pinfunction "4_4") (pintype "passive"))
    )
    (net (code "99") (name "unconnected-(U3-QH-Pad9)") (class "Default")
      (node (ref "U3") (pin "9") (pinfunction "QH_9") (pintype "output"))
    )
    (net (code "100") (name "unconnected-(U4-QH-Pad9)") (class "Default")
      (node (ref "U4") (pin "9") (pinfunction "QH_9") (pintype "output"))
    )
    (net (code "101") (name "unconnected-(U5-QH-Pad9)") (class "Default")
      (node (ref "U5") (pin "9") (pinfunction "QH_9") (pintype "output"))
    )
    (net (code "102") (name "unconnected-(U6-QH'-Pad9)") (class "Default")
      (node (ref "U6") (pin "9") (pinfunction "QH'_9") (pintype "output"))
    )
    (net (code "103") (name "unconnected-(U7-AREF-Pad21)") (class "Default")
      (node (ref "U7") (pin "21") (pinfunction "AREF_21") (pintype "power_in"))
    )
    (net (code "104") (name "unconnected-(U7-PB6_(PCINT6{slash}XTAL1{slash}TOSC1)-Pad9)") (class "Default")
      (node (ref "U7") (pin "9") (pinfunction "PB6_(PCINT6/XTAL1/TOSC1)_9") (pintype "bidirectional"))
    )
    (net (code "105") (name "unconnected-(U7-PB7_(PCINT7{slash}XTAL2{slash}TOSC2)-Pad10)") (class "Default")
      (node (ref "U7") (pin "10") (pinfunction "PB7_(PCINT7/XTAL2/TOSC2)_10") (pintype "bidirectional"))
    )
    (net (code "106") (name "unconnected-(U7-PC0_(ADC0{slash}PCINT8)-Pad23)") (class "Default")
      (node (ref "U7") (pin "23") (pinfunction "PC0_(ADC0/PCINT8)_23") (pintype "bidirectional"))
    )
    (net (code "107") (name "unconnected-(U7-PC3_(ADC3{slash}PCINT11)-Pad26)") (class "Default")
      (node (ref "U7") (pin "26") (pinfunction "PC3_(ADC3/PCINT11)_26") (pintype "bidirectional"))
    )
    (net (code "108") (name "unconnected-(U7-PC4_(ADC4{slash}SDA{slash}PCINT12)-Pad27)") (class "Default")
      (node (ref "U7") (pin "27") (pinfunction "PC4_(ADC4/SDA/PCINT12)_27") (pintype "bidirectional"))
    )
    (net (code "109") (name "unconnected-(U7-PC5_(ADC5{slash}SCL{slash}PCINT13)-Pad28)") (class "Default")
      (node (ref "U7") (pin "28") (pinfunction "PC5_(ADC5/SCL/PCINT13)_28") (pintype "bidirectional"))
    )
    (net (code "110") (name "unconnected-(U7-PC6_(PCINT14{slash}~{RESET})-Pad1)") (class "Default")
      (node (ref "U7") (pin "1") (pinfunction "PC6_(PCINT14/~{RESET})_1") (pintype "bidirectional"))
    )
    (net (code "111") (name "unconnected-(U7-PD0_(PCINT16{slash}RXD)-Pad2)") (class "Default")
      (node (ref "U7") (pin "2") (pinfunction "PD0_(PCINT16/RXD)_2") (pintype "bidirectional"))
    )
    (net (code "112") (name "unconnected-(U7-PD1_(PCINT17{slash}TXD)-Pad3)") (class "Default")
      (node (ref "U7") (pin "3") (pinfunction "PD1_(PCINT17/TXD)_3") (pintype "bidirectional"))
    )
    (net (code "113") (name "unconnected-(U7-PD6_(PCINT22{slash}OC0A{slash}AIN0)-Pad12)") (class "Default")
      (node (ref "U7") (pin "12") (pinfunction "PD6_(PCINT22/OC0A/AIN0)_12") (pintype "bidirectional"))
    )
    (net (code "114") (name "unconnected-(U7-VCC-Pad7)") (class "Default")
      (node (ref "U7") (pin "7") (pinfunction "VCC_7") (pintype "power_in"))
    )
  )
)
